# Speaker_Module_Rev_2.net
KiCad netlist of a schematic drawn in Altium Designer
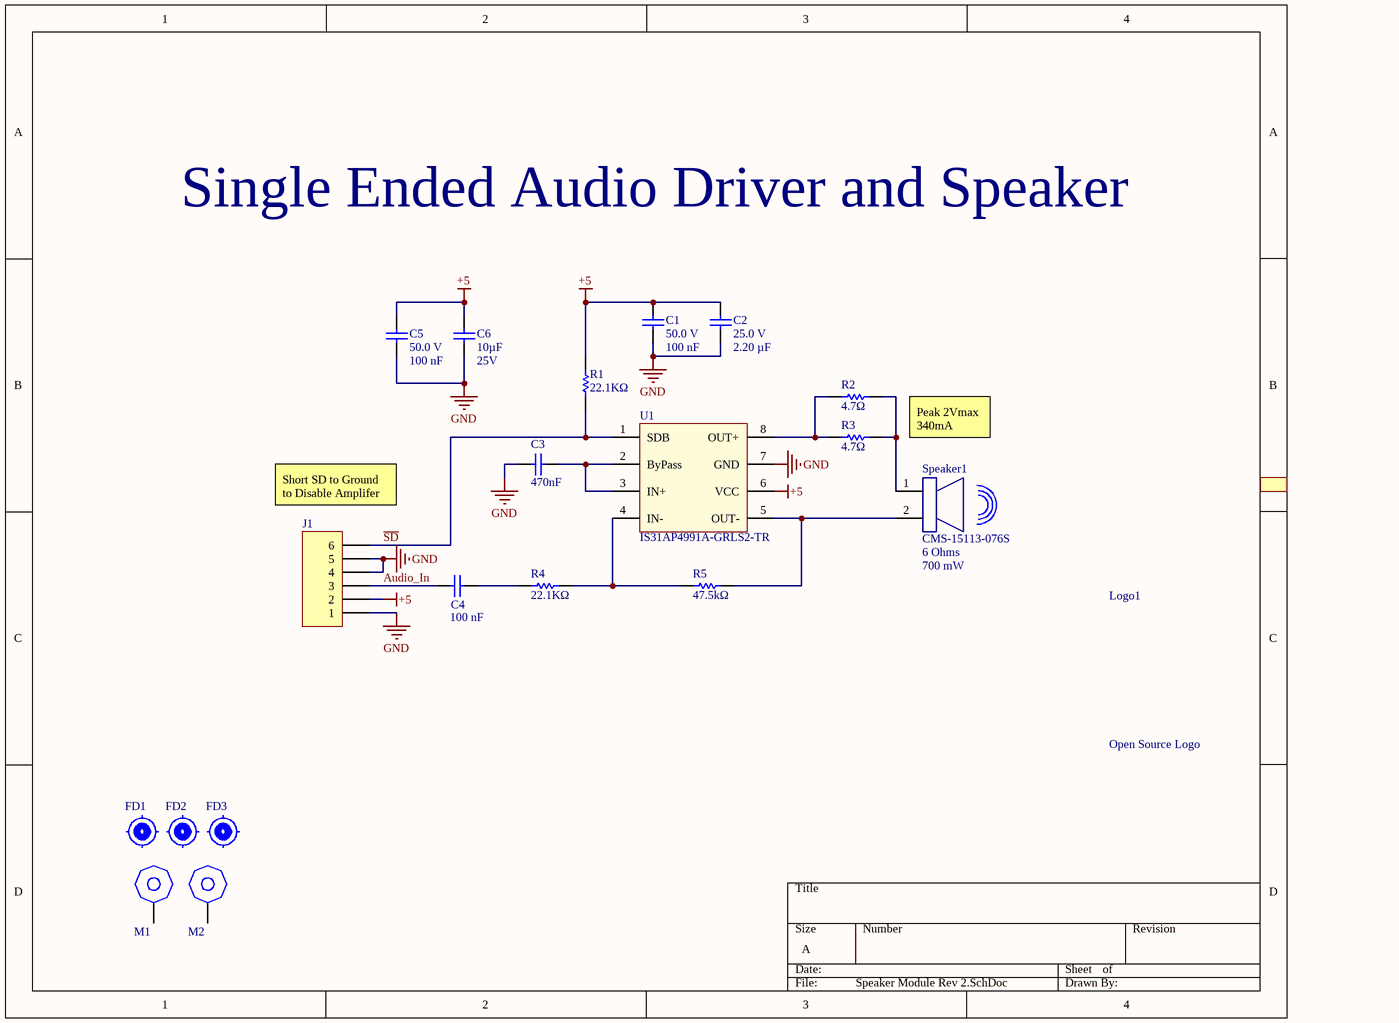
[diagram p0: Speaker Module Rev 2.SchDoc]

(export (version "E")
  (design (tool "Eeschema 10.0.6"))
  (components
    (comp (ref "C1")
      (value "08055C104JAT2A")
      (footprint "Cap,0805")
      (description "Capacitor; Ceramic; Cap 0.1 uF; Tol 5%; Vol-Rtg 50 VDC; SMT; 0805; X7R; Tape & Reel")
      (fields (field (name "VOLTAGE RATING (DC)") "50.0 V") (field (name "CAPACITANCE") "100 nF"))
      (libsource (lib "Master Nov2021") (part "Cap,0805,100nf,50V,5%,08055C104JAT2A"))
    )
    (comp (ref "C2")
      (value "AVX 08053C225KAT2A")
      (footprint "CAP, 0805, HD")
      (description "0805 2.2 uF 25 V ±10 % Tolerance X7R SMT Multilayer Ceramic Capacitor")
      (fields
        (field (name "MANUFACTURER PART NUMBER") "08053C225KAT2A")
        (field (name "VOLTAGE RATING (DC)") "25.0 V")
        (field (name "CAPACITANCE") "2.20 µF")
      )
      (libsource (lib "Master Nov2021") (part "Cap,0805,2.2uF,±10%,25V,08053C225KAT2A"))
    )
    (comp (ref "C3")
      (value "CGA4J2X7R1E474K125AA")
      (footprint "Cap,0805")
      (description "0.47µF ±10% 25V Ceramic Capacitor X7R 0805 (2012 Metric)")
      (fields (field (name "MANUFACTURER") "TDK Corporation") (field (name "CAPACITANCE") "470nF"))
      (libsource (lib "Master Nov2021") (part "Cap,0805,470nf,25V,10%,CGA4J2X7R1E474K125AA"))
    )
    (comp (ref "C4")
      (value "08055C104JAT2A")
      (footprint "Cap,0805")
      (description "Capacitor; Ceramic; Cap 0.1 uF; Tol 5%; Vol-Rtg 50 VDC; SMT; 0805; X7R; Tape & Reel")
      (fields (field (name "CAPACITANCE") "100 nF"))
      (libsource (lib "Master Nov2021") (part "Cap,0805,100nf,50V,5%,08055C104JAT2A"))
    )
    (comp (ref "C5")
      (value "08055C104JAT2A")
      (footprint "Cap,0805")
      (description "Capacitor; Ceramic; Cap 0.1 uF; Tol 5%; Vol-Rtg 50 VDC; SMT; 0805; X7R; Tape & Reel")
      (fields (field (name "VOLTAGE RATING (DC)") "50.0 V") (field (name "CAPACITANCE") "100 nF"))
      (libsource (lib "Master Nov2021") (part "Cap,0805,100nf,50V,5%,08055C104JAT2A"))
    )
    (comp (ref "C6")
      (value "C3216X7R1E106K160AB")
      (footprint "Cap, 1206")
      (description "10µF ±10% 25V Ceramic Capacitor X7R 1206 (3216 Metric)")
      (fields
        (field (name "MANUFACTURER") "TDK Corporation")
        (field (name "TOLERANCE") "±10%")
        (field (name "CAPACITANCE") "10µF")
        (field (name "VOLTAGE - RATED") "25V")
      )
      (libsource (lib "Master Nov2021") (part "CAP,1206,10uF,25V,C3216X7R1E106K160AB"))
    )
    (comp (ref "FD1")
      (value "Mech,FIDU-ROUND")
      (footprint "FIDU-ROUND")
      (description "ROUND FIDUCIAL")
      (libsource (lib "Master Nov2021") (part "Mech,FIDU-ROUND"))
    )
    (comp (ref "FD2")
      (value "Mech,FIDU-ROUND")
      (footprint "FIDU-ROUND")
      (description "ROUND FIDUCIAL")
      (libsource (lib "Master Nov2021") (part "Mech,FIDU-ROUND"))
    )
    (comp (ref "FD3")
      (value "Mech,FIDU-ROUND")
      (footprint "FIDU-ROUND")
      (description "ROUND FIDUCIAL")
      (libsource (lib "Master Nov2021") (part "Mech,FIDU-ROUND"))
    )
    (comp (ref "J1")
      (value "Header, through hole,vertical, 6pin,1 Row,0.1\", M20-9991245")
      (footprint "Header, 6 pin, 0.1\" Spaceing - RA")
      (fields (field (name "MANUFACTURER PART NUMBER") "M20-9990645"))
      (libsource (lib "Master Nov2021") (part "Header, through hole,vertical, 6pin,1 Row,0.1{dblquote}, M20-9991245"))
    )
    (comp (ref "Logo1")
      (value "Open Source Logo")
      (footprint "Symbol,Open Source")
      (description "Open Source Silk Screen Logo")
      (libsource (lib "Master Mar2021") (part "Symbol,Open Source"))
    )
    (comp (ref "M1")
      (value "M3 hex Standoff")
      (footprint "Standoff,Hex,M3,8mm")
      (description "HEX STANDOFF M3,generic")
      (libsource (lib "Master Nov2021") (part "Mech,Standoff, M3, Hex"))
    )
    (comp (ref "M2")
      (value "M3 hex Standoff")
      (footprint "Standoff,Hex,M3,8mm")
      (description "HEX STANDOFF M3,generic")
      (libsource (lib "Master Nov2021") (part "Mech,Standoff, M3, Hex"))
    )
    (comp (ref "R1")
      (value "RC0805FR-0722K1L")
      (footprint "res, 0805, HD")
      (description "22.1 kOhms ±1% 0.125W, 1/8W Chip Resistor 0805 (2012 Metric) Moisture Resistant Thick Film")
      (fields (field (name "RESISTANCE") "22.1KΩ"))
      (libsource (lib "Master Nov2021") (part "Res,0805,22.1K,1%,100ppm,RC0805FR-0722K1L"))
    )
    (comp (ref "R2")
      (value "4.7Ω")
      (footprint "Res,1206")
      (libsource (lib "Master Nov2021") (part "Res,1206,Generic"))
    )
    (comp (ref "R3")
      (value "4.7Ω")
      (footprint "Res,1206")
      (libsource (lib "Master Nov2021") (part "Res,1206,Generic"))
    )
    (comp (ref "R4")
      (value "RC0805FR-0722K1L")
      (footprint "res, 0805, HD")
      (description "22.1 kOhms ±1% 0.125W, 1/8W Chip Resistor 0805 (2012 Metric) Moisture Resistant Thick Film")
      (fields (field (name "RESISTANCE") "22.1KΩ"))
      (libsource (lib "Master Nov2021") (part "Res,0805,22.1K,1%,100ppm,RC0805FR-0722K1L"))
    )
    (comp (ref "R5")
      (value "RK73H2ATTD4752F")
      (footprint "res, 0805, HD")
      (fields
        (field (name "MANUFACTURER") "KOA Speer Electronics, Inc.")
        (field (name "RESISTANCE") "47.5kΩ")
        (field (name "TOLERANCE") "±1%")
      )
      (libsource (lib "Master Nov2021") (part "Res,0805,47.5KΩ,1%,100ppm,RK73H2ATTD4752F"))
    )
    (comp (ref "Speaker1")
      (value "CMS-15113-076S")
      (footprint "Speaker,SMD,CMS-15113-076S")
      (description "6 Ohms General Purpose Speaker 700 mW 100 Hz ~ 20 kHz Top Rectangular")
      (fields
        (field (name "MANUFACTURER") "CUI Devices")
        (field (name "IMPEDANCE") "6 Ohms")
        (field (name "POWER - RATED") "700 mW")
      )
      (libsource (lib "Master Nov2021") (part "Speaker,SMD,6Ω,700mW,Magnetic,100 Hz ~ 20 kHz,CMS-15113-076S"))
    )
    (comp (ref "U1")
      (value "IS31AP4991A-GRLS2-TR")
      (footprint "SOIC-8")
      (description "IC AMP CLASS AB MONO 1.15W 8SOIC")
      (fields (field (name "MFR") "Lumissil Microsystems"))
      (libsource (lib "Master Nov2021") (part "IC,PowerAmp,ClassAB,1.15W x 1 @ 8Ohm,2.7V ~ 5.5V,IS31AP4991"))
    )
  )
  (nets
    (net (code "1") (name "+5") (class "Default")
      (node (ref "C1") (pin "1") (pinfunction "1_1") (pintype "passive"))
      (node (ref "C2") (pin "2") (pinfunction "2_2") (pintype "passive"))
      (node (ref "C5") (pin "1") (pinfunction "1_1") (pintype "passive"))
      (node (ref "C6") (pin "2") (pinfunction "2_2") (pintype "passive"))
      (node (ref "J1") (pin "2") (pinfunction "2_2") (pintype "passive"))
      (node (ref "R1") (pin "1") (pinfunction "1_1") (pintype "passive"))
      (node (ref "U1") (pin "6") (pinfunction "VCC_6") (pintype "passive"))
    )
    (net (code "2") (name "/Audio_In") (class "Default")
      (node (ref "C4") (pin "1") (pinfunction "1_1") (pintype "passive"))
      (node (ref "J1") (pin "3") (pinfunction "3_3") (pintype "passive"))
    )
    (net (code "3") (name "/~{SD}") (class "Default")
      (node (ref "J1") (pin "6") (pinfunction "6_6") (pintype "passive"))
      (node (ref "R1") (pin "2") (pinfunction "2_2") (pintype "passive"))
      (node (ref "U1") (pin "1") (pinfunction "SDB_1") (pintype "passive"))
    )
    (net (code "4") (name "GND") (class "Default")
      (node (ref "C1") (pin "2") (pinfunction "2_2") (pintype "passive"))
      (node (ref "C2") (pin "1") (pinfunction "1_1") (pintype "passive"))
      (node (ref "C3") (pin "2") (pinfunction "2_2") (pintype "passive"))
      (node (ref "C5") (pin "2") (pinfunction "2_2") (pintype "passive"))
      (node (ref "C6") (pin "1") (pinfunction "1_1") (pintype "passive"))
      (node (ref "J1") (pin "1") (pinfunction "1_1") (pintype "passive"))
      (node (ref "J1") (pin "4") (pinfunction "4_4") (pintype "passive"))
      (node (ref "J1") (pin "5") (pinfunction "5_5") (pintype "passive"))
      (node (ref "U1") (pin "7") (pinfunction "GND_7") (pintype "passive"))
    )
    (net (code "5") (name "Net-(C4-Pad2)") (class "Default")
      (node (ref "C4") (pin "2") (pinfunction "2_2") (pintype "passive"))
      (node (ref "R4") (pin "2") (pinfunction "2_2") (pintype "passive"))
    )
    (net (code "6") (name "Net-(R2-Pad1)") (class "Default")
      (node (ref "R2") (pin "1") (pinfunction "1_1") (pintype "passive"))
      (node (ref "R3") (pin "1") (pinfunction "1_1") (pintype "passive"))
      (node (ref "Speaker1") (pin "1") (pinfunction "1_1") (pintype "passive"))
    )
    (net (code "7") (name "Net-(U1-ByPass)") (class "Default")
      (node (ref "C3") (pin "1") (pinfunction "1_1") (pintype "passive"))
      (node (ref "U1") (pin "2") (pinfunction "ByPass_2") (pintype "passive"))
      (node (ref "U1") (pin "3") (pinfunction "IN+_3") (pintype "passive"))
    )
    (net (code "8") (name "Net-(U1-IN-)") (class "Default")
      (node (ref "R4") (pin "1") (pinfunction "1_1") (pintype "passive"))
      (node (ref "R5") (pin "2") (pinfunction "2_2") (pintype "passive"))
      (node (ref "U1") (pin "4") (pinfunction "IN-_4") (pintype "passive"))
    )
    (net (code "9") (name "Net-(U1-OUT+)") (class "Default")
      (node (ref "R2") (pin "2") (pinfunction "2_2") (pintype "passive"))
      (node (ref "R3") (pin "2") (pinfunction "2_2") (pintype "passive"))
      (node (ref "U1") (pin "8") (pinfunction "OUT+_8") (pintype "passive"))
    )
    (net (code "10") (name "Net-(U1-OUT-)") (class "Default")
      (node (ref "R5") (pin "1") (pinfunction "1_1") (pintype "passive"))
      (node (ref "Speaker1") (pin "2") (pinfunction "2_2") (pintype "passive"))
      (node (ref "U1") (pin "5") (pinfunction "OUT-_5") (pintype "passive"))
    )
    (net (code "11") (name "unconnected-(M1-Pad0)") (class "Default")
      (node (ref "M1") (pin "0") (pinfunction "0_0") (pintype "passive"))
    )
    (net (code "12") (name "unconnected-(M2-Pad0)") (class "Default")
      (node (ref "M2") (pin "0") (pinfunction "0_0") (pintype "passive"))
    )
  )
)
